# qtpy_synth_proto2b.net
KiCad netlist of a schematic drawn in EAGLE
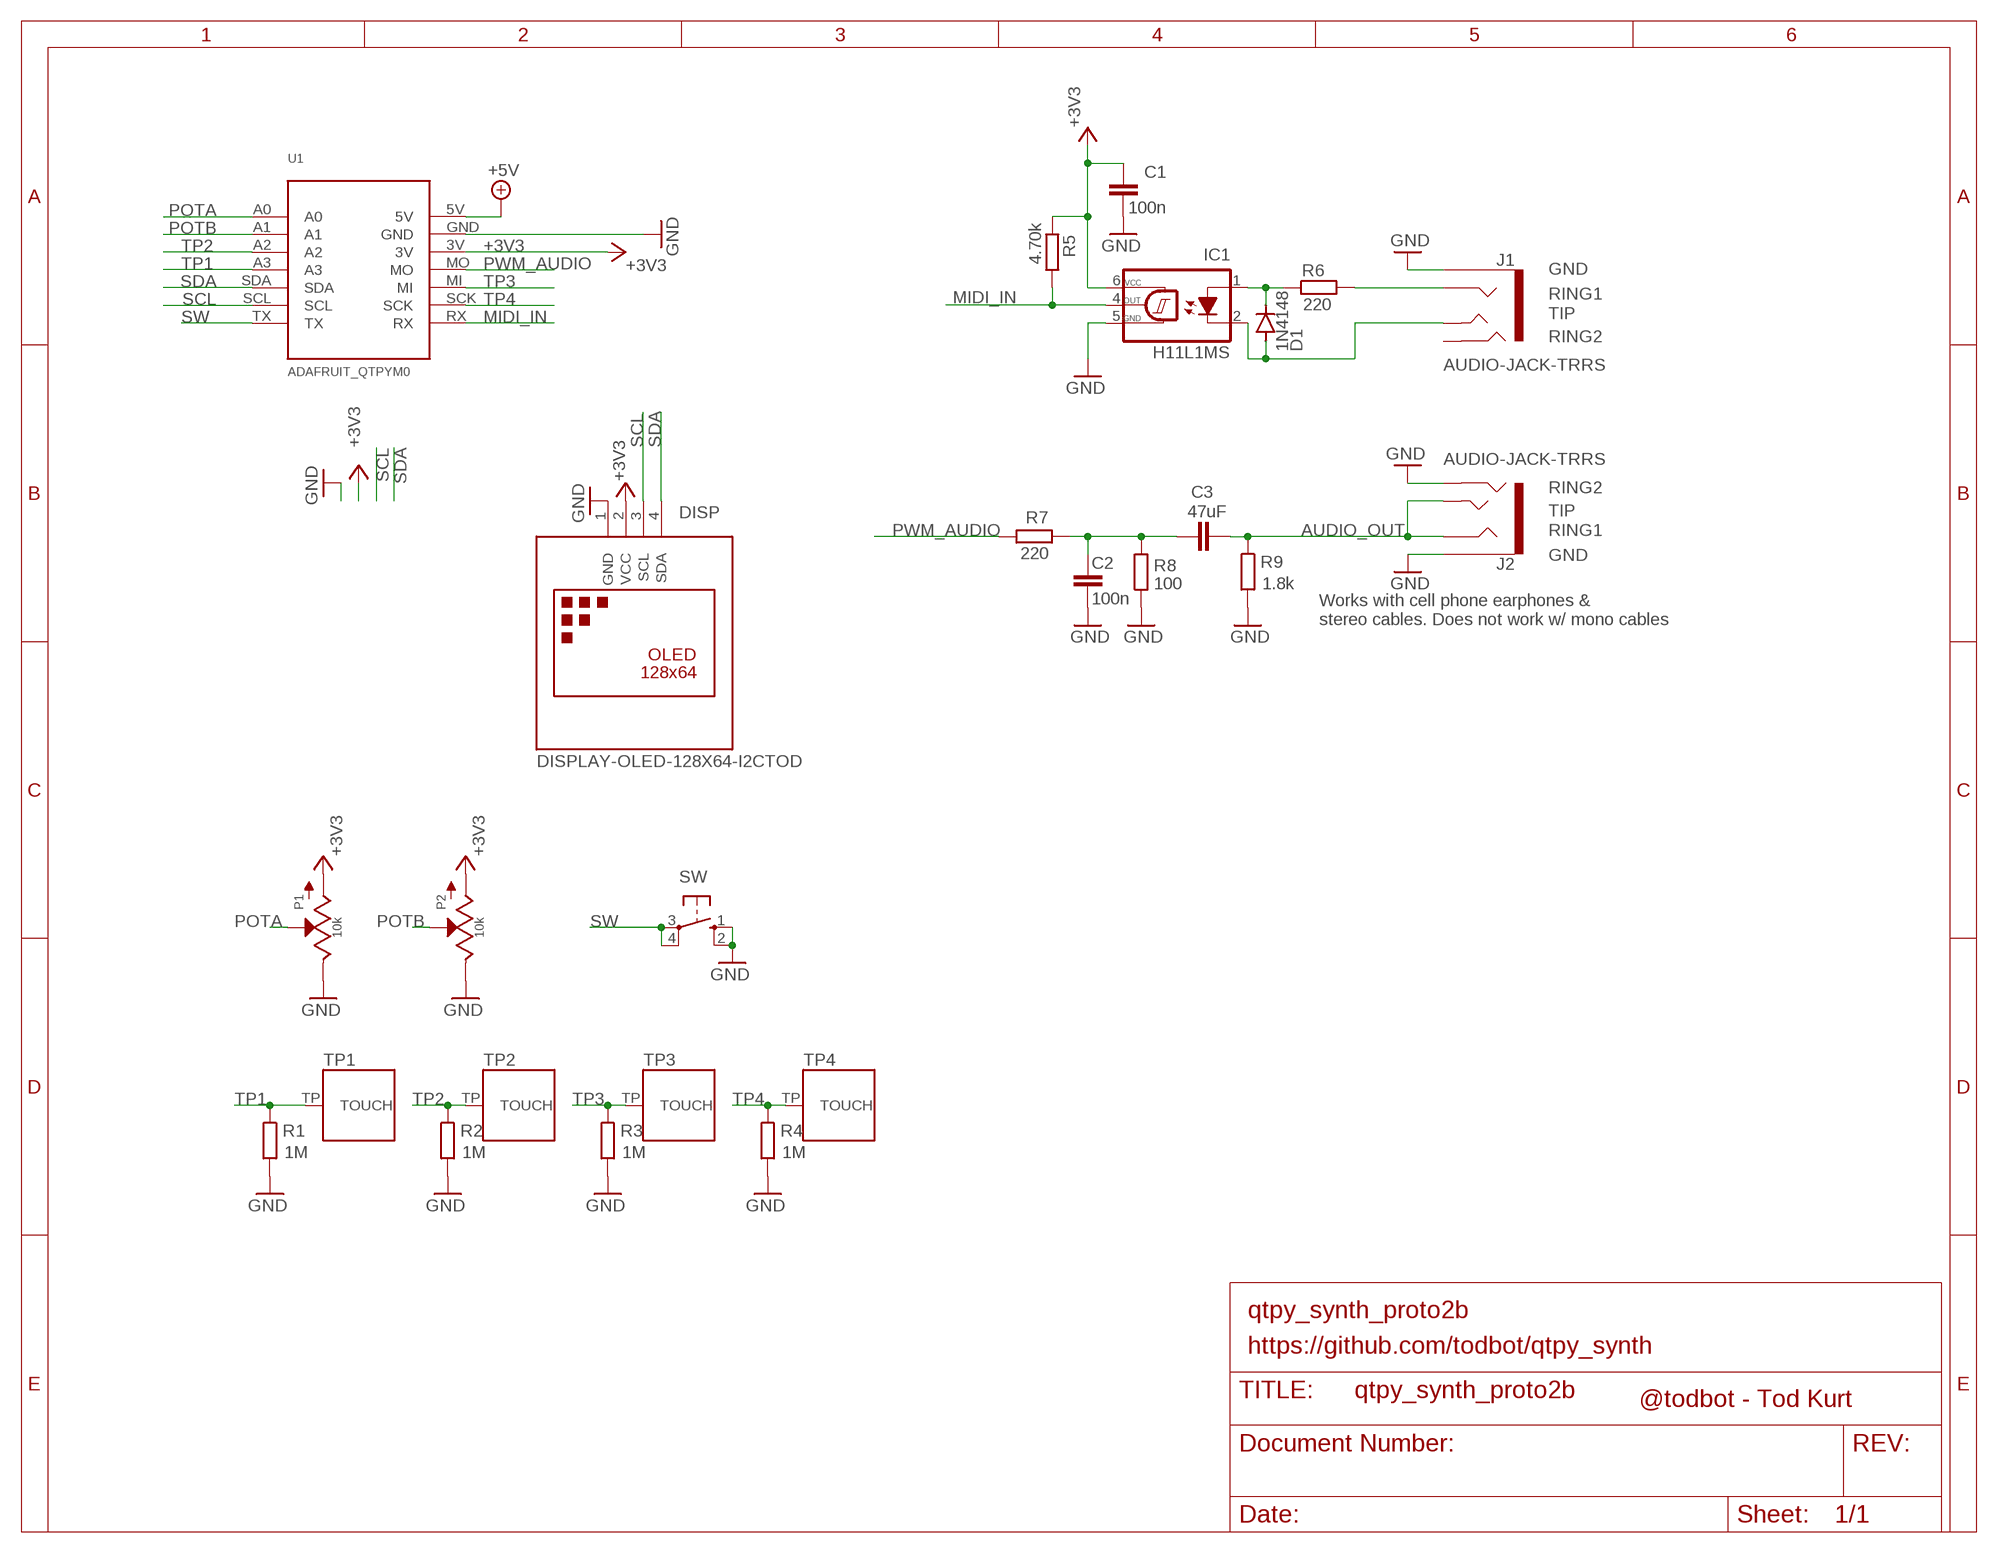
[diagram p0: schematic, sheet 1]

(export (version "E")
  (design (tool "Eeschema 10.0.6"))
  (components
    (comp (ref "C1")
      (value "100n")
      (footprint "eagle-import:C0805")
      (libsource (lib "eagle-import") (part "C-EUC0805"))
    )
    (comp (ref "C2")
      (value "100n")
      (footprint "eagle-import:C0805")
      (libsource (lib "eagle-import") (part "C-EUC0805"))
    )
    (comp (ref "C3")
      (value "47uF")
      (footprint "eagle-import:C0805")
      (libsource (lib "eagle-import") (part "C-EUC0805"))
    )
    (comp (ref "D1")
      (value "1N4148")
      (footprint "eagle-import:SOD123")
      (libsource (lib "eagle-import") (part "DIODE-SOD123"))
    )
    (comp (ref "DISP")
      (value "DISPLAY-OLED-128X64-I2CTOD")
      (footprint "eagle-import:DISPLAY-OLED-128X64-I2C-TOD")
      (libsource (lib "eagle-import") (part "DISPLAY-OLED-128X64-I2CTOD"))
    )
    (comp (ref "IC1")
      (value "H11L1MS")
      (footprint "eagle-import:DIL6-SMD")
      (libsource (lib "eagle-import") (part "H11LMS1"))
    )
    (comp (ref "J1")
      (value "AUDIO-JACK-TRRS")
      (footprint "eagle-import:PJ-320D_SPARKFUN")
      (fields (field (name "MPN") "PJ-320D"))
      (libsource (lib "eagle-import") (part "AUDIO-JACK-TRRS"))
    )
    (comp (ref "J2")
      (value "AUDIO-JACK-TRRS")
      (footprint "eagle-import:PJ-320D_SPARKFUN")
      (fields (field (name "MPN") "PJ-320D") (field (name "LCSC") "C431535"))
      (libsource (lib "eagle-import") (part "AUDIO-JACK-TRRS"))
    )
    (comp (ref "P1")
      (value "10k")
      (footprint "eagle-import:OG-POTS_ALPS_POT_VERTICAL_WITHBIGKNOB")
      (libsource (lib "eagle-import") (part "POTZEPHPOT_BIGKNOB"))
    )
    (comp (ref "P2")
      (value "10k")
      (footprint "eagle-import:OG-POTS_ALPS_POT_VERTICAL_WITHBIGKNOB")
      (libsource (lib "eagle-import") (part "POTZEPHPOT_BIGKNOB"))
    )
    (comp (ref "R1")
      (value "1M")
      (footprint "eagle-import:R0805")
      (libsource (lib "eagle-import") (part "R-EU_R0805"))
    )
    (comp (ref "R2")
      (value "1M")
      (footprint "eagle-import:R0805")
      (libsource (lib "eagle-import") (part "R-EU_R0805"))
    )
    (comp (ref "R3")
      (value "1M")
      (footprint "eagle-import:R0805")
      (libsource (lib "eagle-import") (part "R-EU_R0805"))
    )
    (comp (ref "R4")
      (value "1M")
      (footprint "eagle-import:R0805")
      (libsource (lib "eagle-import") (part "R-EU_R0805"))
    )
    (comp (ref "R5")
      (value "4.70k")
      (footprint "eagle-import:R0805")
      (libsource (lib "eagle-import") (part "R-EU_R0805"))
    )
    (comp (ref "R6")
      (value "220")
      (footprint "eagle-import:R0805")
      (libsource (lib "eagle-import") (part "R-EU_R0805"))
    )
    (comp (ref "R7")
      (value "220")
      (footprint "eagle-import:R0805")
      (libsource (lib "eagle-import") (part "R-EU_R0805"))
    )
    (comp (ref "R8")
      (value "100")
      (footprint "eagle-import:R0805")
      (libsource (lib "eagle-import") (part "R-EU_R0805"))
    )
    (comp (ref "R9")
      (value "1.8k")
      (footprint "eagle-import:R0805")
      (libsource (lib "eagle-import") (part "R-EU_R0805"))
    )
    (comp (ref "SW")
      (value "10-XX")
      (footprint "eagle-import:B3F-10XX")
      (fields (field (name "MPN") "B3F-1000"))
      (libsource (lib "eagle-import") (part "10-XX"))
    )
    (comp (ref "TP1")
      (value "TOUCHPADA")
      (footprint "eagle-import:TOUCHPADA_0.5IN")
      (libsource (lib "eagle-import") (part "TOUCHPADA"))
    )
    (comp (ref "TP2")
      (value "TOUCHPADA")
      (footprint "eagle-import:TOUCHPADA_0.5IN")
      (libsource (lib "eagle-import") (part "TOUCHPADA"))
    )
    (comp (ref "TP3")
      (value "TOUCHPADA")
      (footprint "eagle-import:TOUCHPADA_0.5IN")
      (libsource (lib "eagle-import") (part "TOUCHPADA"))
    )
    (comp (ref "TP4")
      (value "TOUCHPADA")
      (footprint "eagle-import:TOUCHPADA_0.5IN")
      (libsource (lib "eagle-import") (part "TOUCHPADA"))
    )
    (comp (ref "U1")
      (value "ADAFRUIT_QTPYM0")
      (footprint "eagle-import:ADAFRUIT_QTPY_M0")
      (libsource (lib "eagle-import") (part "ADAFRUIT_QTPYM0"))
    )
  )
  (nets
    (net (code "1") (name "+3V3") (class "Default")
      (node (ref "C1") (pin "1") (pinfunction "1_1") (pintype "passive"))
      (node (ref "DISP") (pin "2") (pinfunction "VCC_2") (pintype "power_in"))
      (node (ref "IC1") (pin "6") (pinfunction "VCC_6") (pintype "power_in"))
      (node (ref "P1") (pin "P$3") (pinfunction "A_P$3") (pintype "passive"))
      (node (ref "P2") (pin "P$3") (pinfunction "A_P$3") (pintype "passive"))
      (node (ref "R5") (pin "1") (pinfunction "1_1") (pintype "passive"))
      (node (ref "U1") (pin "3V") (pinfunction "3V_3V") (pintype "bidirectional"))
    )
    (net (code "2") (name "+5V") (class "Default")
      (node (ref "U1") (pin "5V") (pinfunction "5V_5V") (pintype "bidirectional"))
    )
    (net (code "3") (name "/AUDIO_OUT") (class "Default")
      (node (ref "C3") (pin "2") (pinfunction "2_2") (pintype "passive"))
      (node (ref "J2") (pin "RING1") (pinfunction "RING1_RING1") (pintype "bidirectional"))
      (node (ref "J2") (pin "TIP") (pinfunction "TIP_TIP") (pintype "bidirectional"))
      (node (ref "R9") (pin "1") (pinfunction "1_1") (pintype "passive"))
    )
    (net (code "4") (name "/MIDI_IN") (class "Default")
      (node (ref "IC1") (pin "4") (pinfunction "OUT_4") (pintype "output"))
      (node (ref "R5") (pin "2") (pinfunction "2_2") (pintype "passive"))
      (node (ref "U1") (pin "RX") (pinfunction "RX_RX") (pintype "bidirectional"))
    )
    (net (code "5") (name "/POTA") (class "Default")
      (node (ref "P1") (pin "P$2") (pinfunction "S_P$2") (pintype "passive"))
      (node (ref "U1") (pin "A0") (pinfunction "A0_A0") (pintype "bidirectional"))
    )
    (net (code "6") (name "/POTB") (class "Default")
      (node (ref "P2") (pin "P$2") (pinfunction "S_P$2") (pintype "passive"))
      (node (ref "U1") (pin "A1") (pinfunction "A1_A1") (pintype "bidirectional"))
    )
    (net (code "7") (name "/PWM_AUDIO") (class "Default")
      (node (ref "R7") (pin "2") (pinfunction "2_2") (pintype "passive"))
      (node (ref "U1") (pin "MO") (pinfunction "MO_MO") (pintype "bidirectional"))
    )
    (net (code "8") (name "/SCL") (class "Default")
      (node (ref "DISP") (pin "3") (pinfunction "SCL_3") (pintype "bidirectional"))
      (node (ref "U1") (pin "SCL") (pinfunction "SCL_SCL") (pintype "bidirectional"))
    )
    (net (code "9") (name "/SDA") (class "Default")
      (node (ref "DISP") (pin "4") (pinfunction "SDA_4") (pintype "bidirectional"))
      (node (ref "U1") (pin "SDA") (pinfunction "SDA_SDA") (pintype "bidirectional"))
    )
    (net (code "10") (name "/SW") (class "Default")
      (node (ref "SW") (pin "3") (pinfunction "P_3") (pintype "passive"))
      (node (ref "SW") (pin "4") (pinfunction "P1_4") (pintype "passive"))
      (node (ref "U1") (pin "TX") (pinfunction "TX_TX") (pintype "bidirectional"))
    )
    (net (code "11") (name "/TP1") (class "Default")
      (node (ref "R1") (pin "1") (pinfunction "1_1") (pintype "passive"))
      (node (ref "TP1") (pin "TP") (pinfunction "TOUCH_TP") (pintype "bidirectional"))
      (node (ref "U1") (pin "A3") (pinfunction "A3_A3") (pintype "bidirectional"))
    )
    (net (code "12") (name "/TP2") (class "Default")
      (node (ref "R2") (pin "1") (pinfunction "1_1") (pintype "passive"))
      (node (ref "TP2") (pin "TP") (pinfunction "TOUCH_TP") (pintype "bidirectional"))
      (node (ref "U1") (pin "A2") (pinfunction "A2_A2") (pintype "bidirectional"))
    )
    (net (code "13") (name "/TP3") (class "Default")
      (node (ref "R3") (pin "1") (pinfunction "1_1") (pintype "passive"))
      (node (ref "TP3") (pin "TP") (pinfunction "TOUCH_TP") (pintype "bidirectional"))
      (node (ref "U1") (pin "MI") (pinfunction "MI_MI") (pintype "bidirectional"))
    )
    (net (code "14") (name "/TP4") (class "Default")
      (node (ref "R4") (pin "1") (pinfunction "1_1") (pintype "passive"))
      (node (ref "TP4") (pin "TP") (pinfunction "TOUCH_TP") (pintype "bidirectional"))
      (node (ref "U1") (pin "SCK") (pinfunction "SCK_SCK") (pintype "bidirectional"))
    )
    (net (code "15") (name "GND") (class "Default")
      (node (ref "C1") (pin "2") (pinfunction "2_2") (pintype "passive"))
      (node (ref "C2") (pin "2") (pinfunction "2_2") (pintype "passive"))
      (node (ref "DISP") (pin "1") (pinfunction "GND_1") (pintype "power_in"))
      (node (ref "IC1") (pin "5") (pinfunction "GND_5") (pintype "power_in"))
      (node (ref "J1") (pin "EARTH") (pinfunction "EARTH_EARTH") (pintype "bidirectional"))
      (node (ref "J2") (pin "EARTH") (pinfunction "EARTH_EARTH") (pintype "bidirectional"))
      (node (ref "J2") (pin "RING2") (pinfunction "RING2_RING2") (pintype "bidirectional"))
      (node (ref "P1") (pin "P$1") (pinfunction "E_P$1") (pintype "passive"))
      (node (ref "P2") (pin "P$1") (pinfunction "E_P$1") (pintype "passive"))
      (node (ref "R1") (pin "2") (pinfunction "2_2") (pintype "passive"))
      (node (ref "R2") (pin "2") (pinfunction "2_2") (pintype "passive"))
      (node (ref "R3") (pin "2") (pinfunction "2_2") (pintype "passive"))
      (node (ref "R4") (pin "2") (pinfunction "2_2") (pintype "passive"))
      (node (ref "R8") (pin "1") (pinfunction "1_1") (pintype "passive"))
      (node (ref "R9") (pin "2") (pinfunction "2_2") (pintype "passive"))
      (node (ref "SW") (pin "1") (pinfunction "S_1") (pintype "passive"))
      (node (ref "SW") (pin "2") (pinfunction "S1_2") (pintype "passive"))
      (node (ref "U1") (pin "GND") (pinfunction "GND_GND") (pintype "bidirectional"))
    )
    (net (code "16") (name "Net-(C2-Pad1)") (class "Default")
      (node (ref "C2") (pin "1") (pinfunction "1_1") (pintype "passive"))
      (node (ref "C3") (pin "1") (pinfunction "1_1") (pintype "passive"))
      (node (ref "R7") (pin "1") (pinfunction "1_1") (pintype "passive"))
      (node (ref "R8") (pin "2") (pinfunction "2_2") (pintype "passive"))
    )
    (net (code "17") (name "Net-(IC1-A)") (class "Default")
      (node (ref "D1") (pin "C") (pinfunction "C_C") (pintype "passive"))
      (node (ref "IC1") (pin "1") (pinfunction "A_1") (pintype "passive"))
      (node (ref "R6") (pin "1") (pinfunction "1_1") (pintype "passive"))
    )
    (net (code "18") (name "Net-(IC1-C)") (class "Default")
      (node (ref "D1") (pin "A") (pinfunction "A_A") (pintype "passive"))
      (node (ref "IC1") (pin "2") (pinfunction "C_2") (pintype "passive"))
      (node (ref "J1") (pin "TIP") (pinfunction "TIP_TIP") (pintype "bidirectional"))
    )
    (net (code "19") (name "Net-(J1-PadRING1)") (class "Default")
      (node (ref "J1") (pin "RING1") (pinfunction "RING1_RING1") (pintype "bidirectional"))
      (node (ref "R6") (pin "2") (pinfunction "2_2") (pintype "passive"))
    )
    (net (code "20") (name "unconnected-(J1-PadRING2)") (class "Default")
      (node (ref "J1") (pin "RING2") (pinfunction "RING2_RING2") (pintype "bidirectional"))
    )
  )
)
